# lebcube1.net
KiCad netlist of a schematic drawn in Altium Designer
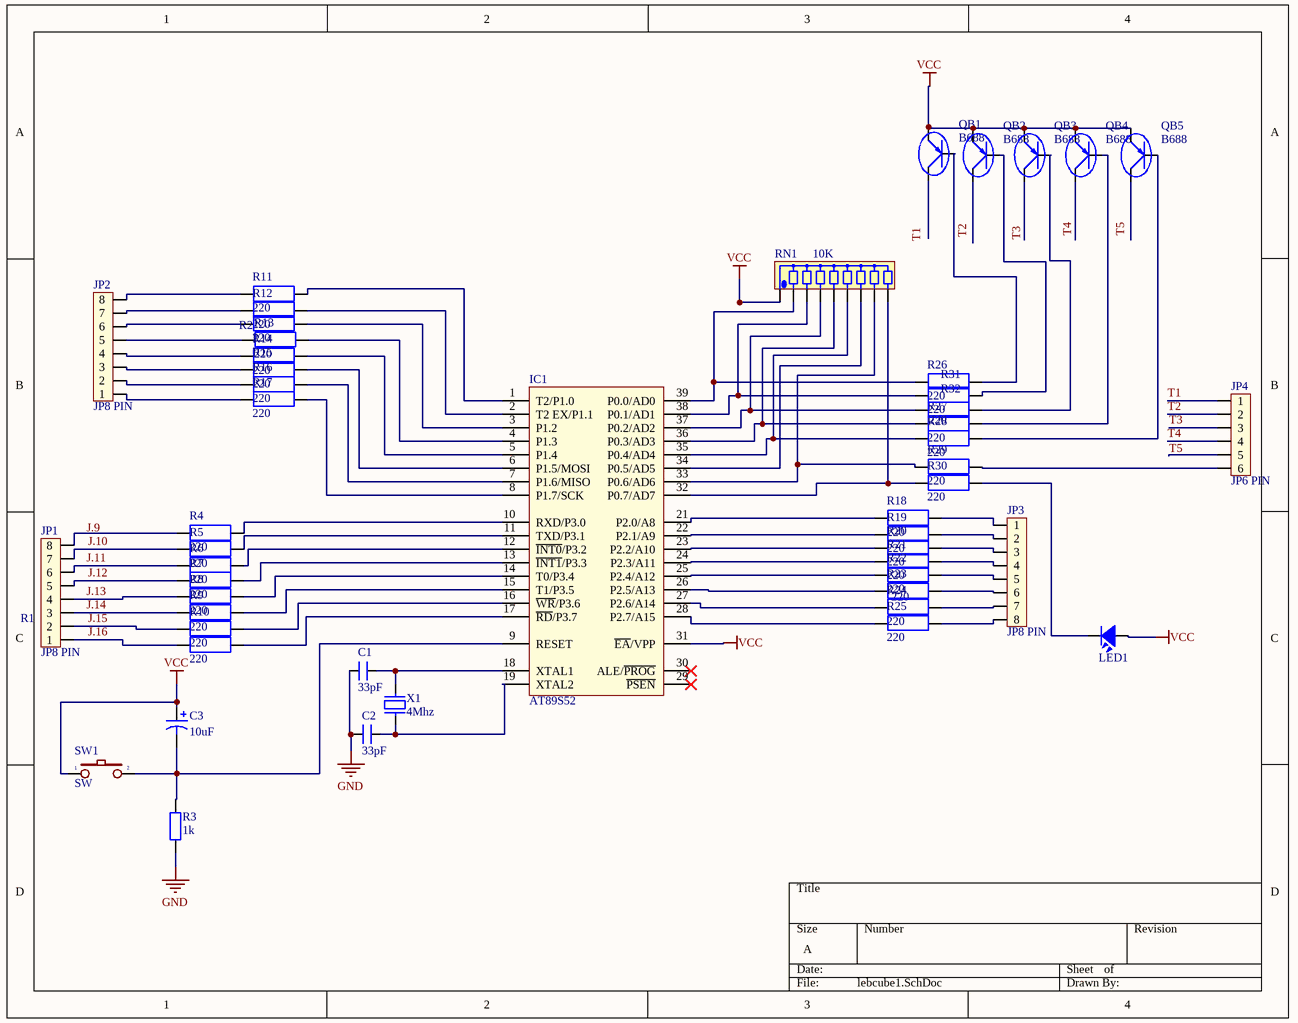
[diagram p0: lebcube1.SchDoc]

(export (version "E")
  (design (tool "Eeschema 10.0.6"))
  (components
    (comp (ref "C1")
      (value "33pF")
      (footprint "CN1")
      (description "Cap np  1pF - 472pF")
      (libsource (lib "syhaunguyen") (part "CN1"))
    )
    (comp (ref "C2")
      (value "33pF")
      (footprint "CN1")
      (description "Cap np  1pF - 472pF")
      (libsource (lib "syhaunguyen") (part "CN1"))
    )
    (comp (ref "C3")
      (value "10uF")
      (footprint "CP2/5")
      (description "Polarized Capacitor (Surface Mount)")
      (fields (field (name "PUBLISHER") "Altium Limited"))
      (libsource (lib "syhaunguyen") (part "Cap Pol3"))
    )
    (comp (ref "IC1")
      (value "AT89S52")
      (footprint "DIP40/W0.6")
      (description "AT89S52, 8k Byte Flash Memory , 40 Pin")
      (libsource (lib "Cty1") (part "AT89S52"))
    )
    (comp (ref "JP1") (value "JP8 PIN") (footprint "JP8") (libsource (lib "syhaunguyen") (part "JP8")))
    (comp (ref "JP2") (value "JP8 PIN") (footprint "JP8") (libsource (lib "syhaunguyen") (part "JP8")))
    (comp (ref "JP3") (value "JP8 PIN") (footprint "JP8") (libsource (lib "") (part "JP8_1")))
    (comp (ref "JP4") (value "JP6 PIN") (footprint "JP6") (libsource (lib "syhaunguyen") (part "JP6")))
    (comp (ref "LED1")
      (value "LED")
      (footprint "LED-3")
      (description "LED Single colour Green and Red")
      (libsource (lib "syhaunguyen") (part "LED"))
    )
    (comp (ref "QB1")
      (value "B688")
      (footprint "QTO-247")
      (description "Transistor Power Supply")
      (libsource (lib "syhaunguyen") (part "B688"))
    )
    (comp (ref "QB2")
      (value "B688")
      (footprint "QTO-247")
      (description "Transistor Power Supply")
      (libsource (lib "syhaunguyen") (part "B688"))
    )
    (comp (ref "QB3")
      (value "B688")
      (footprint "QTO-247")
      (description "Transistor Power Supply")
      (libsource (lib "syhaunguyen") (part "B688"))
    )
    (comp (ref "QB4")
      (value "B688")
      (footprint "QTO-247")
      (description "Transistor Power Supply")
      (libsource (lib "syhaunguyen") (part "B688"))
    )
    (comp (ref "QB5")
      (value "B688")
      (footprint "QTO-247")
      (description "Transistor Power Supply")
      (libsource (lib "syhaunguyen") (part "B688"))
    )
    (comp (ref "R1")
      (value "220")
      (footprint "R1W")
      (description "Resistor 1W")
      (libsource (lib "syhaunguyen") (part "R1W"))
    )
    (comp (ref "R2")
      (value "220")
      (footprint "R1W")
      (description "Resistor 1W")
      (libsource (lib "syhaunguyen") (part "R1W"))
    )
    (comp (ref "R3")
      (value "1k")
      (footprint "R1/4W")
      (description "Resistor 1/4W")
      (libsource (lib "syhaunguyen") (part "R1/4W"))
    )
    (comp (ref "R4")
      (value "220")
      (footprint "R1W")
      (description "Resistor 1W")
      (libsource (lib "syhaunguyen") (part "R1W"))
    )
    (comp (ref "R5")
      (value "220")
      (footprint "R1W")
      (description "Resistor 1W")
      (libsource (lib "syhaunguyen") (part "R1W"))
    )
    (comp (ref "R6")
      (value "220")
      (footprint "R1W")
      (description "Resistor 1W")
      (libsource (lib "syhaunguyen") (part "R1W"))
    )
    (comp (ref "R7")
      (value "220")
      (footprint "R1W")
      (description "Resistor 1W")
      (libsource (lib "syhaunguyen") (part "R1W"))
    )
    (comp (ref "R8")
      (value "220")
      (footprint "R1W")
      (description "Resistor 1W")
      (libsource (lib "syhaunguyen") (part "R1W"))
    )
    (comp (ref "R9")
      (value "220")
      (footprint "R1W")
      (description "Resistor 1W")
      (libsource (lib "syhaunguyen") (part "R1W"))
    )
    (comp (ref "R10")
      (value "220")
      (footprint "R1W")
      (description "Resistor 1W")
      (libsource (lib "syhaunguyen") (part "R1W"))
    )
    (comp (ref "R11")
      (value "220")
      (footprint "R1W")
      (description "Resistor 1W")
      (libsource (lib "syhaunguyen") (part "R1W"))
    )
    (comp (ref "R12")
      (value "220")
      (footprint "R1W")
      (description "Resistor 1W")
      (libsource (lib "syhaunguyen") (part "R1W"))
    )
    (comp (ref "R13")
      (value "220")
      (footprint "R1W")
      (description "Resistor 1W")
      (libsource (lib "syhaunguyen") (part "R1W"))
    )
    (comp (ref "R14")
      (value "220")
      (footprint "R1W")
      (description "Resistor 1W")
      (libsource (lib "syhaunguyen") (part "R1W"))
    )
    (comp (ref "R15")
      (value "220")
      (footprint "R1W")
      (description "Resistor 1W")
      (libsource (lib "syhaunguyen") (part "R1W"))
    )
    (comp (ref "R16")
      (value "220")
      (footprint "R1W")
      (description "Resistor 1W")
      (libsource (lib "syhaunguyen") (part "R1W"))
    )
    (comp (ref "R17")
      (value "220")
      (footprint "R1W")
      (description "Resistor 1W")
      (libsource (lib "syhaunguyen") (part "R1W"))
    )
    (comp (ref "R18")
      (value "220")
      (footprint "R1W")
      (description "Resistor 1W")
      (libsource (lib "syhaunguyen") (part "R1W"))
    )
    (comp (ref "R19")
      (value "220")
      (footprint "R1W")
      (description "Resistor 1W")
      (libsource (lib "syhaunguyen") (part "R1W"))
    )
    (comp (ref "R20")
      (value "220")
      (footprint "R1W")
      (description "Resistor 1W")
      (libsource (lib "syhaunguyen") (part "R1W"))
    )
    (comp (ref "R21")
      (value "220")
      (footprint "R1W")
      (description "Resistor 1W")
      (libsource (lib "syhaunguyen") (part "R1W"))
    )
    (comp (ref "R22")
      (value "220")
      (footprint "R1W")
      (description "Resistor 1W")
      (libsource (lib "syhaunguyen") (part "R1W"))
    )
    (comp (ref "R23")
      (value "220")
      (footprint "R1W")
      (description "Resistor 1W")
      (libsource (lib "syhaunguyen") (part "R1W"))
    )
    (comp (ref "R24")
      (value "220")
      (footprint "R1W")
      (description "Resistor 1W")
      (libsource (lib "syhaunguyen") (part "R1W"))
    )
    (comp (ref "R25")
      (value "220")
      (footprint "R1W")
      (description "Resistor 1W")
      (libsource (lib "syhaunguyen") (part "R1W"))
    )
    (comp (ref "R26")
      (value "220")
      (footprint "R1W")
      (description "Resistor 1W")
      (libsource (lib "syhaunguyen") (part "R1W"))
    )
    (comp (ref "R27")
      (value "220")
      (footprint "R1W")
      (description "Resistor 1W")
      (libsource (lib "syhaunguyen") (part "R1W"))
    )
    (comp (ref "R28")
      (value "220")
      (footprint "R1W")
      (description "Resistor 1W")
      (libsource (lib "syhaunguyen") (part "R1W"))
    )
    (comp (ref "R29")
      (value "220")
      (footprint "R1W")
      (description "Resistor 1W")
      (libsource (lib "syhaunguyen") (part "R1W"))
    )
    (comp (ref "R30")
      (value "220")
      (footprint "R1W")
      (description "Resistor 1W")
      (libsource (lib "syhaunguyen") (part "R1W"))
    )
    (comp (ref "R31")
      (value "220")
      (footprint "R1W")
      (description "Resistor 1W")
      (libsource (lib "syhaunguyen") (part "R1W"))
    )
    (comp (ref "R32")
      (value "220")
      (footprint "R1W")
      (description "Resistor 1W")
      (libsource (lib "syhaunguyen") (part "R1W"))
    )
    (comp (ref "RN1")
      (value "10K")
      (footprint "RN8")
      (description "Resistor 8 (Thanh)")
      (libsource (lib "syhaunguyen") (part "RN8"))
    )
    (comp (ref "SW1")
      (value "SW")
      (footprint "SW2")
      (description "Switch button 2 pin")
      (libsource (lib "syhaunguyen") (part "SW2"))
    )
    (comp (ref "X1")
      (value "4Mhz")
      (footprint "XT2")
      (description "Crystal For all Crystal 2pin.")
      (libsource (lib "syhaunguyen") (part "XT2"))
    )
  )
  (nets
    (net (code "2") (name "/J.10") (class "Default")
      (node (ref "JP1") (pin "7") (pinfunction "7_7") (pintype "passive"))
      (node (ref "R5") (pin "1") (pinfunction "1_1") (pintype "passive"))
    )
    (net (code "3") (name "/J.11") (class "Default")
      (node (ref "JP1") (pin "6") (pinfunction "6_6") (pintype "passive"))
      (node (ref "R6") (pin "1") (pinfunction "1_1") (pintype "passive"))
    )
    (net (code "4") (name "/J.12") (class "Default")
      (node (ref "JP1") (pin "5") (pinfunction "5_5") (pintype "passive"))
      (node (ref "R7") (pin "1") (pinfunction "1_1") (pintype "passive"))
    )
    (net (code "5") (name "/J.13") (class "Default")
      (node (ref "JP1") (pin "4") (pinfunction "4_4") (pintype "passive"))
      (node (ref "R8") (pin "1") (pinfunction "1_1") (pintype "passive"))
    )
    (net (code "6") (name "/J.14") (class "Default")
      (node (ref "JP1") (pin "3") (pinfunction "3_3") (pintype "passive"))
      (node (ref "R9") (pin "1") (pinfunction "1_1") (pintype "passive"))
    )
    (net (code "7") (name "/J.15") (class "Default")
      (node (ref "JP1") (pin "2") (pinfunction "2_2") (pintype "passive"))
      (node (ref "R10") (pin "1") (pinfunction "1_1") (pintype "passive"))
    )
    (net (code "8") (name "/J.16") (class "Default")
      (node (ref "JP1") (pin "1") (pinfunction "1_1") (pintype "passive"))
      (node (ref "R1") (pin "1") (pinfunction "1_1") (pintype "passive"))
    )
    (net (code "9") (name "/T1") (class "Default")
      (node (ref "JP4") (pin "1") (pinfunction "1_1") (pintype "passive"))
    )
    (net (code "10") (name "/T2") (class "Default")
      (node (ref "JP4") (pin "2") (pinfunction "2_2") (pintype "passive"))
    )
    (net (code "11") (name "/T3") (class "Default")
      (node (ref "JP4") (pin "3") (pinfunction "3_3") (pintype "passive"))
      (node (ref "QB3") (pin "2") (pinfunction "C_2") (pintype "passive"))
    )
    (net (code "12") (name "/T4") (class "Default")
      (node (ref "JP4") (pin "4") (pinfunction "4_4") (pintype "passive"))
      (node (ref "QB4") (pin "2") (pinfunction "C_2") (pintype "passive"))
    )
    (net (code "13") (name "/T5") (class "Default")
      (node (ref "JP4") (pin "5") (pinfunction "5_5") (pintype "passive"))
    )
    (net (code "14") (name "GND") (class "Default")
      (node (ref "C1") (pin "1") (pinfunction "1_1") (pintype "passive"))
      (node (ref "C2") (pin "1") (pinfunction "1_1") (pintype "passive"))
      (node (ref "IC1") (pin "20") (pinfunction "GND_20") (pintype "power_in"))
      (node (ref "R3") (pin "2") (pinfunction "2_2") (pintype "passive"))
    )
    (net (code "15") (name "Net-(IC1-P0.0{slash}AD0)") (class "Default")
      (node (ref "IC1") (pin "39") (pinfunction "P0.0/AD0_39") (pintype "passive"))
      (node (ref "R26") (pin "1") (pinfunction "1_1") (pintype "passive"))
      (node (ref "RN1") (pin "2") (pinfunction "2_2") (pintype "passive"))
    )
    (net (code "16") (name "Net-(IC1-P0.1{slash}AD1)") (class "Default")
      (node (ref "IC1") (pin "38") (pinfunction "P0.1/AD1_38") (pintype "passive"))
      (node (ref "R31") (pin "1") (pinfunction "1_1") (pintype "passive"))
      (node (ref "RN1") (pin "3") (pinfunction "3_3") (pintype "passive"))
    )
    (net (code "17") (name "Net-(IC1-P0.2{slash}AD2)") (class "Default")
      (node (ref "IC1") (pin "37") (pinfunction "P0.2/AD2_37") (pintype "passive"))
      (node (ref "R32") (pin "1") (pinfunction "1_1") (pintype "passive"))
      (node (ref "RN1") (pin "4") (pinfunction "4_4") (pintype "passive"))
    )
    (net (code "18") (name "Net-(IC1-P0.3{slash}AD3)") (class "Default")
      (node (ref "IC1") (pin "36") (pinfunction "P0.3/AD3_36") (pintype "passive"))
      (node (ref "R27") (pin "1") (pinfunction "1_1") (pintype "passive"))
      (node (ref "RN1") (pin "5") (pinfunction "5_5") (pintype "passive"))
    )
    (net (code "19") (name "Net-(IC1-P0.4{slash}AD4)") (class "Default")
      (node (ref "IC1") (pin "35") (pinfunction "P0.4/AD4_35") (pintype "passive"))
      (node (ref "R28") (pin "1") (pinfunction "1_1") (pintype "passive"))
      (node (ref "RN1") (pin "6") (pinfunction "6_6") (pintype "passive"))
    )
    (net (code "20") (name "Net-(IC1-P0.5{slash}AD5)") (class "Default")
      (node (ref "IC1") (pin "34") (pinfunction "P0.5/AD5_34") (pintype "passive"))
      (node (ref "RN1") (pin "7") (pinfunction "7_7") (pintype "passive"))
    )
    (net (code "21") (name "Net-(IC1-P0.6{slash}AD6)") (class "Default")
      (node (ref "IC1") (pin "33") (pinfunction "P0.6/AD6_33") (pintype "passive"))
      (node (ref "R29") (pin "1") (pinfunction "1_1") (pintype "passive"))
      (node (ref "RN1") (pin "8") (pinfunction "8_8") (pintype "passive"))
    )
    (net (code "22") (name "Net-(IC1-P0.7{slash}AD7)") (class "Default")
      (node (ref "IC1") (pin "32") (pinfunction "P0.7/AD7_32") (pintype "passive"))
      (node (ref "R30") (pin "1") (pinfunction "1_1") (pintype "passive"))
      (node (ref "RN1") (pin "9") (pinfunction "9_9") (pintype "passive"))
    )
    (net (code "23") (name "Net-(IC1-P1.2)") (class "Default")
      (node (ref "IC1") (pin "3") (pinfunction "P1.2_3") (pintype "passive"))
      (node (ref "R2") (pin "2") (pinfunction "2_2") (pintype "passive"))
    )
    (net (code "24") (name "Net-(IC1-P1.3)") (class "Default")
      (node (ref "IC1") (pin "4") (pinfunction "P1.3_4") (pintype "passive"))
      (node (ref "R13") (pin "2") (pinfunction "2_2") (pintype "passive"))
    )
    (net (code "25") (name "Net-(IC1-P1.4)") (class "Default")
      (node (ref "IC1") (pin "5") (pinfunction "P1.4_5") (pintype "passive"))
      (node (ref "R14") (pin "2") (pinfunction "2_2") (pintype "passive"))
    )
    (net (code "26") (name "Net-(IC1-P1.5{slash}MOSI)") (class "Default")
      (node (ref "IC1") (pin "6") (pinfunction "P1.5/MOSI_6") (pintype "passive"))
      (node (ref "R15") (pin "2") (pinfunction "2_2") (pintype "passive"))
    )
    (net (code "27") (name "Net-(IC1-P1.6{slash}MISO)") (class "Default")
      (node (ref "IC1") (pin "7") (pinfunction "P1.6/MISO_7") (pintype "passive"))
      (node (ref "R16") (pin "2") (pinfunction "2_2") (pintype "passive"))
    )
    (net (code "28") (name "Net-(IC1-P1.7{slash}SCK)") (class "Default")
      (node (ref "IC1") (pin "8") (pinfunction "P1.7/SCK_8") (pintype "passive"))
      (node (ref "R17") (pin "2") (pinfunction "2_2") (pintype "passive"))
    )
    (net (code "29") (name "Net-(IC1-P2.0{slash}A8)") (class "Default")
      (node (ref "IC1") (pin "21") (pinfunction "P2.0/A8_21") (pintype "passive"))
      (node (ref "R18") (pin "1") (pinfunction "1_1") (pintype "passive"))
    )
    (net (code "30") (name "Net-(IC1-P2.1{slash}A9)") (class "Default")
      (node (ref "IC1") (pin "22") (pinfunction "P2.1/A9_22") (pintype "passive"))
      (node (ref "R19") (pin "1") (pinfunction "1_1") (pintype "passive"))
    )
    (net (code "31") (name "Net-(IC1-P2.2{slash}A10)") (class "Default")
      (node (ref "IC1") (pin "23") (pinfunction "P2.2/A10_23") (pintype "passive"))
      (node (ref "R20") (pin "1") (pinfunction "1_1") (pintype "passive"))
    )
    (net (code "32") (name "Net-(IC1-P2.3{slash}A11)") (class "Default")
      (node (ref "IC1") (pin "24") (pinfunction "P2.3/A11_24") (pintype "passive"))
      (node (ref "R21") (pin "1") (pinfunction "1_1") (pintype "passive"))
    )
    (net (code "33") (name "Net-(IC1-P2.4{slash}A12)") (class "Default")
      (node (ref "IC1") (pin "25") (pinfunction "P2.4/A12_25") (pintype "passive"))
      (node (ref "R22") (pin "1") (pinfunction "1_1") (pintype "passive"))
    )
    (net (code "34") (name "Net-(IC1-P2.5{slash}A13)") (class "Default")
      (node (ref "IC1") (pin "26") (pinfunction "P2.5/A13_26") (pintype "passive"))
      (node (ref "R23") (pin "1") (pinfunction "1_1") (pintype "passive"))
    )
    (net (code "35") (name "Net-(IC1-P2.6{slash}A14)") (class "Default")
      (node (ref "IC1") (pin "27") (pinfunction "P2.6/A14_27") (pintype "passive"))
      (node (ref "R24") (pin "1") (pinfunction "1_1") (pintype "passive"))
    )
    (net (code "36") (name "Net-(IC1-P2.7{slash}A15)") (class "Default")
      (node (ref "IC1") (pin "28") (pinfunction "P2.7/A15_28") (pintype "passive"))
      (node (ref "R25") (pin "1") (pinfunction "1_1") (pintype "passive"))
    )
    (net (code "37") (name "Net-(IC1-RESET)") (class "Default")
      (node (ref "C3") (pin "2") (pinfunction "2_2") (pintype "passive"))
      (node (ref "IC1") (pin "9") (pinfunction "RESET_9") (pintype "passive"))
      (node (ref "R3") (pin "1") (pinfunction "1_1") (pintype "passive"))
      (node (ref "SW1") (pin "2") (pinfunction "2_2") (pintype "passive"))
    )
    (net (code "38") (name "Net-(IC1-RXD{slash}P3.0)") (class "Default")
      (node (ref "IC1") (pin "10") (pinfunction "RXD/P3.0_10") (pintype "passive"))
      (node (ref "R4") (pin "2") (pinfunction "2_2") (pintype "passive"))
    )
    (net (code "39") (name "Net-(IC1-T0{slash}P3.4)") (class "Default")
      (node (ref "IC1") (pin "14") (pinfunction "T0/P3.4_14") (pintype "passive"))
      (node (ref "R8") (pin "2") (pinfunction "2_2") (pintype "passive"))
    )
    (net (code "40") (name "Net-(IC1-T1{slash}P3.5)") (class "Default")
      (node (ref "IC1") (pin "15") (pinfunction "T1/P3.5_15") (pintype "passive"))
      (node (ref "R9") (pin "2") (pinfunction "2_2") (pintype "passive"))
    )
    (net (code "41") (name "Net-(IC1-T2_EX{slash}P1.1)") (class "Default")
      (node (ref "IC1") (pin "2") (pinfunction "T2_EX/P1.1_2") (pintype "passive"))
      (node (ref "R12") (pin "2") (pinfunction "2_2") (pintype "passive"))
    )
    (net (code "42") (name "Net-(IC1-T2{slash}P1.0)") (class "Default")
      (node (ref "IC1") (pin "1") (pinfunction "T2/P1.0_1") (pintype "passive"))
      (node (ref "R11") (pin "2") (pinfunction "2_2") (pintype "passive"))
    )
    (net (code "43") (name "Net-(IC1-TXD{slash}P3.1)") (class "Default")
      (node (ref "IC1") (pin "11") (pinfunction "TXD/P3.1_11") (pintype "passive"))
      (node (ref "R5") (pin "2") (pinfunction "2_2") (pintype "passive"))
    )
    (net (code "44") (name "Net-(IC1-XTAL1)") (class "Default")
      (node (ref "C1") (pin "2") (pinfunction "2_2") (pintype "passive"))
      (node (ref "IC1") (pin "18") (pinfunction "XTAL1_18") (pintype "passive"))
      (node (ref "X1") (pin "1") (pinfunction "1_1") (pintype "passive"))
    )
    (net (code "45") (name "Net-(IC1-XTAL2)") (class "Default")
      (node (ref "C2") (pin "2") (pinfunction "2_2") (pintype "passive"))
      (node (ref "IC1") (pin "19") (pinfunction "XTAL2_19") (pintype "passive"))
      (node (ref "X1") (pin "2") (pinfunction "2_2") (pintype "passive"))
    )
    (net (code "46") (name "Net-(IC1-~{INT0}{slash}P3.2)") (class "Default")
      (node (ref "IC1") (pin "12") (pinfunction "~{INT0}/P3.2_12") (pintype "passive"))
      (node (ref "R6") (pin "2") (pinfunction "2_2") (pintype "passive"))
    )
    (net (code "47") (name "Net-(IC1-~{INT1}{slash}P3.3)") (class "Default")
      (node (ref "IC1") (pin "13") (pinfunction "~{INT1}/P3.3_13") (pintype "passive"))
      (node (ref "R7") (pin "2") (pinfunction "2_2") (pintype "passive"))
    )
    (net (code "48") (name "Net-(IC1-~{RD}{slash}P3.7)") (class "Default")
      (node (ref "IC1") (pin "17") (pinfunction "~{RD}/P3.7_17") (pintype "passive"))
      (node (ref "R1") (pin "2") (pinfunction "2_2") (pintype "passive"))
    )
    (net (code "49") (name "Net-(IC1-~{WR}{slash}P3.6)") (class "Default")
      (node (ref "IC1") (pin "16") (pinfunction "~{WR}/P3.6_16") (pintype "passive"))
      (node (ref "R10") (pin "2") (pinfunction "2_2") (pintype "passive"))
    )
    (net (code "50") (name "Net-(JP1-Pad8)") (class "Default")
      (node (ref "JP1") (pin "8") (pinfunction "8_8") (pintype "passive"))
      (node (ref "R4") (pin "1") (pinfunction "1_1") (pintype "passive"))
    )
    (net (code "51") (name "Net-(JP2-Pad1)") (class "Default")
      (node (ref "JP2") (pin "1") (pinfunction "1_1") (pintype "passive"))
      (node (ref "R17") (pin "1") (pinfunction "1_1") (pintype "passive"))
    )
    (net (code "52") (name "Net-(JP2-Pad2)") (class "Default")
      (node (ref "JP2") (pin "2") (pinfunction "2_2") (pintype "passive"))
      (node (ref "R16") (pin "1") (pinfunction "1_1") (pintype "passive"))
    )
    (net (code "53") (name "Net-(JP2-Pad3)") (class "Default")
      (node (ref "JP2") (pin "3") (pinfunction "3_3") (pintype "passive"))
      (node (ref "R15") (pin "1") (pinfunction "1_1") (pintype "passive"))
    )
    (net (code "54") (name "Net-(JP2-Pad4)") (class "Default")
      (node (ref "JP2") (pin "4") (pinfunction "4_4") (pintype "passive"))
      (node (ref "R14") (pin "1") (pinfunction "1_1") (pintype "passive"))
    )
    (net (code "55") (name "Net-(JP2-Pad5)") (class "Default")
      (node (ref "JP2") (pin "5") (pinfunction "5_5") (pintype "passive"))
      (node (ref "R13") (pin "1") (pinfunction "1_1") (pintype "passive"))
    )
    (net (code "56") (name "Net-(JP2-Pad6)") (class "Default")
      (node (ref "JP2") (pin "6") (pinfunction "6_6") (pintype "passive"))
      (node (ref "R2") (pin "1") (pinfunction "1_1") (pintype "passive"))
    )
    (net (code "57") (name "Net-(JP2-Pad7)") (class "Default")
      (node (ref "JP2") (pin "7") (pinfunction "7_7") (pintype "passive"))
      (node (ref "R12") (pin "1") (pinfunction "1_1") (pintype "passive"))
    )
    (net (code "58") (name "Net-(JP2-Pad8)") (class "Default")
      (node (ref "JP2") (pin "8") (pinfunction "8_8") (pintype "passive"))
      (node (ref "R11") (pin "1") (pinfunction "1_1") (pintype "passive"))
    )
    (net (code "59") (name "Net-(JP3-Pad1)") (class "Default")
      (node (ref "JP3") (pin "1") (pinfunction "1_1") (pintype "passive"))
      (node (ref "R18") (pin "2") (pinfunction "2_2") (pintype "passive"))
    )
    (net (code "60") (name "Net-(JP3-Pad2)") (class "Default")
      (node (ref "JP3") (pin "2") (pinfunction "2_2") (pintype "passive"))
      (node (ref "R19") (pin "2") (pinfunction "2_2") (pintype "passive"))
    )
    (net (code "61") (name "Net-(JP3-Pad3)") (class "Default")
      (node (ref "JP3") (pin "3") (pinfunction "3_3") (pintype "passive"))
      (node (ref "R20") (pin "2") (pinfunction "2_2") (pintype "passive"))
    )
    (net (code "62") (name "Net-(JP3-Pad4)") (class "Default")
      (node (ref "JP3") (pin "4") (pinfunction "4_4") (pintype "passive"))
      (node (ref "R21") (pin "2") (pinfunction "2_2") (pintype "passive"))
    )
    (net (code "63") (name "Net-(JP3-Pad5)") (class "Default")
      (node (ref "JP3") (pin "5") (pinfunction "5_5") (pintype "passive"))
      (node (ref "R22") (pin "2") (pinfunction "2_2") (pintype "passive"))
    )
    (net (code "64") (name "Net-(JP3-Pad6)") (class "Default")
      (node (ref "JP3") (pin "6") (pinfunction "6_6") (pintype "passive"))
      (node (ref "R23") (pin "2") (pinfunction "2_2") (pintype "passive"))
    )
    (net (code "65") (name "Net-(JP3-Pad7)") (class "Default")
      (node (ref "JP3") (pin "7") (pinfunction "7_7") (pintype "passive"))
      (node (ref "R24") (pin "2") (pinfunction "2_2") (pintype "passive"))
    )
    (net (code "66") (name "Net-(JP3-Pad8)") (class "Default")
      (node (ref "JP3") (pin "8") (pinfunction "8_8") (pintype "passive"))
      (node (ref "R25") (pin "2") (pinfunction "2_2") (pintype "passive"))
    )
    (net (code "67") (name "Net-(JP4-Pad6)") (class "Default")
      (node (ref "JP4") (pin "6") (pinfunction "6_6") (pintype "passive"))
      (node (ref "R29") (pin "2") (pinfunction "2_2") (pintype "passive"))
    )
    (net (code "68") (name "Net-(LED1-Pad2)") (class "Default")
      (node (ref "LED1") (pin "2") (pinfunction "2_2") (pintype "passive"))
      (node (ref "R30") (pin "2") (pinfunction "2_2") (pintype "passive"))
    )
    (net (code "69") (name "Net-(QB1-B)") (class "Default")
      (node (ref "QB1") (pin "1") (pinfunction "B_1") (pintype "passive"))
      (node (ref "R26") (pin "2") (pinfunction "2_2") (pintype "passive"))
    )
    (net (code "70") (name "Net-(QB2-B)") (class "Default")
      (node (ref "QB2") (pin "1") (pinfunction "B_1") (pintype "passive"))
      (node (ref "R31") (pin "2") (pinfunction "2_2") (pintype "passive"))
    )
    (net (code "71") (name "Net-(QB3-B)") (class "Default")
      (node (ref "QB3") (pin "1") (pinfunction "B_1") (pintype "passive"))
      (node (ref "R32") (pin "2") (pinfunction "2_2") (pintype "passive"))
    )
    (net (code "72") (name "Net-(QB4-B)") (class "Default")
      (node (ref "QB4") (pin "1") (pinfunction "B_1") (pintype "passive"))
      (node (ref "R27") (pin "2") (pinfunction "2_2") (pintype "passive"))
    )
    (net (code "73") (name "Net-(QB5-B)") (class "Default")
      (node (ref "QB5") (pin "1") (pinfunction "B_1") (pintype "passive"))
      (node (ref "R28") (pin "2") (pinfunction "2_2") (pintype "passive"))
    )
    (net (code "74") (name "VCC") (class "Default")
      (node (ref "C3") (pin "1") (pinfunction "1_1") (pintype "passive"))
      (node (ref "IC1") (pin "31") (pinfunction "~{EA}/VPP_31") (pintype "passive"))
      (node (ref "IC1") (pin "40") (pinfunction "VCC_40") (pintype "power_in"))
      (node (ref "LED1") (pin "1") (pinfunction "1_1") (pintype "passive"))
      (node (ref "QB1") (pin "3") (pinfunction "E_3") (pintype "passive"))
      (node (ref "QB2") (pin "3") (pinfunction "E_3") (pintype "passive"))
      (node (ref "QB3") (pin "3") (pinfunction "E_3") (pintype "passive"))
      (node (ref "QB4") (pin "3") (pinfunction "E_3") (pintype "passive"))
      (node (ref "QB5") (pin "3") (pinfunction "E_3") (pintype "passive"))
      (node (ref "RN1") (pin "1") (pinfunction "1_1") (pintype "passive"))
      (node (ref "SW1") (pin "1") (pinfunction "1_1") (pintype "passive"))
    )
    (net (code "75") (name "unconnected-(IC1-ALE{slash}~{PROG}-Pad30)") (class "Default")
      (node (ref "IC1") (pin "30") (pinfunction "ALE/~{PROG}_30") (pintype "passive+no_connect"))
    )
    (net (code "76") (name "unconnected-(IC1-~{PSEN}-Pad29)") (class "Default")
      (node (ref "IC1") (pin "29") (pinfunction "~{PSEN}_29") (pintype "passive+no_connect"))
    )
    (net (code "77") (name "unconnected-(QB1-C-Pad2)") (class "Default")
      (node (ref "QB1") (pin "2") (pinfunction "C_2") (pintype "passive"))
    )
    (net (code "78") (name "unconnected-(QB2-C-Pad2)") (class "Default")
      (node (ref "QB2") (pin "2") (pinfunction "C_2") (pintype "passive"))
    )
    (net (code "79") (name "unconnected-(QB5-C-Pad2)") (class "Default")
      (node (ref "QB5") (pin "2") (pinfunction "C_2") (pintype "passive"))
    )
  )
)
